# PMXAS5600N12_V1_0.net
KiCad netlist of a schematic drawn in EAGLE
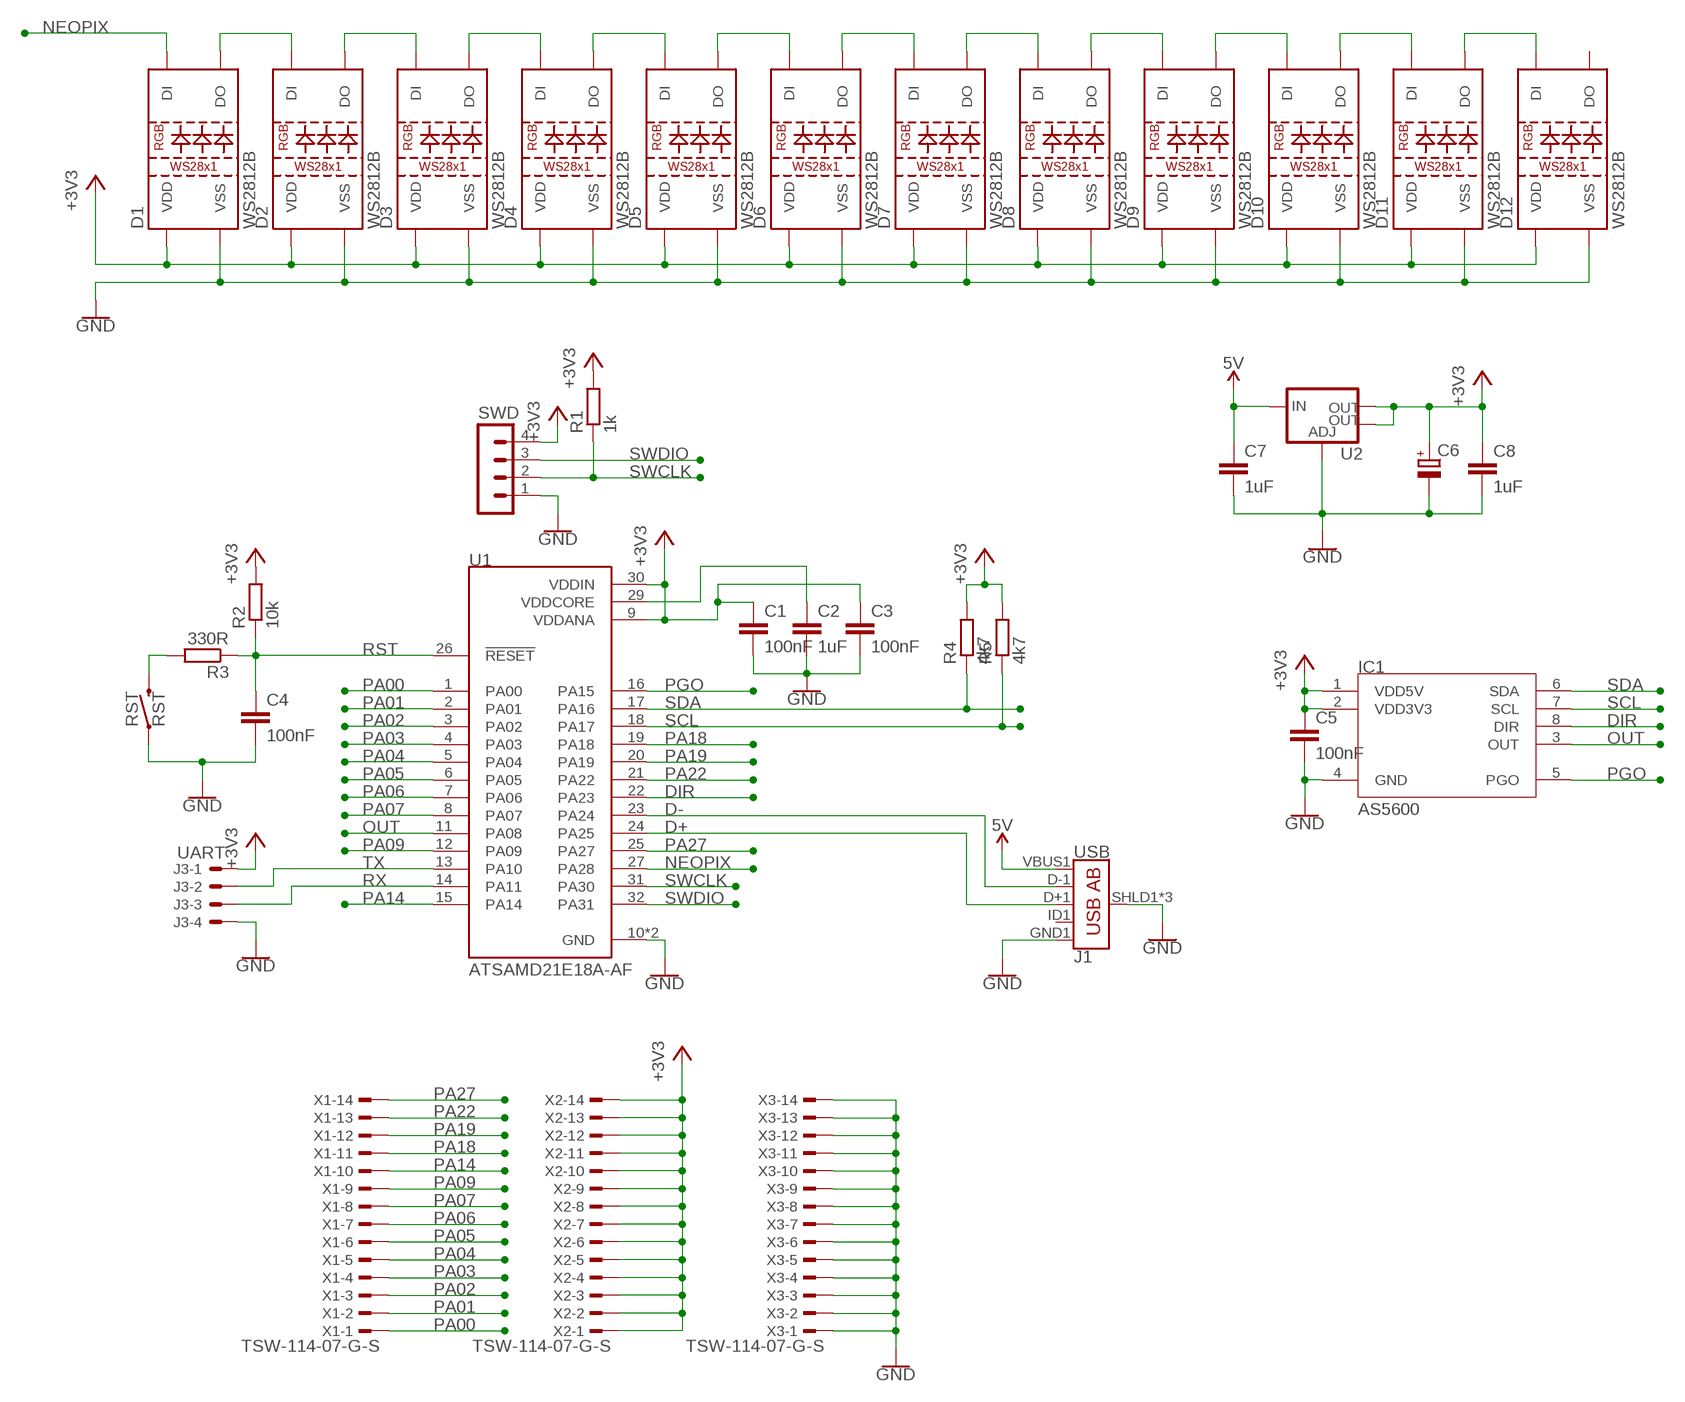
[diagram p0: schematic, sheet 1]

(export (version "E")
  (design (tool "Eeschema 10.0.6"))
  (components
    (comp (ref "C1")
      (value "100nF")
      (footprint "eagle-import:C0603")
      (libsource (lib "eagle-import") (part "C-EUC0603"))
    )
    (comp (ref "C2")
      (value "1uF")
      (footprint "eagle-import:C0603")
      (libsource (lib "eagle-import") (part "C-EUC0603"))
    )
    (comp (ref "C3")
      (value "100nF")
      (footprint "eagle-import:C0603")
      (libsource (lib "eagle-import") (part "C-EUC0603"))
    )
    (comp (ref "C4")
      (value "100nF")
      (footprint "eagle-import:C0603")
      (libsource (lib "eagle-import") (part "C-EUC0603"))
    )
    (comp (ref "C5")
      (value "100nF")
      (footprint "eagle-import:C0603")
      (libsource (lib "eagle-import") (part "C-EUC0603"))
    )
    (comp (ref "C6")
      (value "CPOL-EU153CLV-0605")
      (footprint "eagle-import:153CLV-0605")
      (libsource (lib "eagle-import") (part "CPOL-EU153CLV-0605"))
    )
    (comp (ref "C7")
      (value "1uF")
      (footprint "eagle-import:C0603")
      (libsource (lib "eagle-import") (part "C-EUC0603"))
    )
    (comp (ref "C8")
      (value "1uF")
      (footprint "eagle-import:C0603")
      (libsource (lib "eagle-import") (part "C-EUC0603"))
    )
    (comp (ref "D1")
      (value "WS2812B")
      (footprint "eagle-import:WS2812B")
      (libsource (lib "eagle-import") (part "WS2812B"))
    )
    (comp (ref "D2")
      (value "WS2812B")
      (footprint "eagle-import:WS2812B")
      (libsource (lib "eagle-import") (part "WS2812B"))
    )
    (comp (ref "D3")
      (value "WS2812B")
      (footprint "eagle-import:WS2812B")
      (libsource (lib "eagle-import") (part "WS2812B"))
    )
    (comp (ref "D4")
      (value "WS2812B")
      (footprint "eagle-import:WS2812B")
      (libsource (lib "eagle-import") (part "WS2812B"))
    )
    (comp (ref "D5")
      (value "WS2812B")
      (footprint "eagle-import:WS2812B")
      (libsource (lib "eagle-import") (part "WS2812B"))
    )
    (comp (ref "D6")
      (value "WS2812B")
      (footprint "eagle-import:WS2812B")
      (libsource (lib "eagle-import") (part "WS2812B"))
    )
    (comp (ref "D7")
      (value "WS2812B")
      (footprint "eagle-import:WS2812B")
      (libsource (lib "eagle-import") (part "WS2812B"))
    )
    (comp (ref "D8")
      (value "WS2812B")
      (footprint "eagle-import:WS2812B")
      (libsource (lib "eagle-import") (part "WS2812B"))
    )
    (comp (ref "D9")
      (value "WS2812B")
      (footprint "eagle-import:WS2812B")
      (libsource (lib "eagle-import") (part "WS2812B"))
    )
    (comp (ref "D10")
      (value "WS2812B")
      (footprint "eagle-import:WS2812B")
      (libsource (lib "eagle-import") (part "WS2812B"))
    )
    (comp (ref "D11")
      (value "WS2812B")
      (footprint "eagle-import:WS2812B")
      (libsource (lib "eagle-import") (part "WS2812B"))
    )
    (comp (ref "D12")
      (value "WS2812B")
      (footprint "eagle-import:WS2812B")
      (libsource (lib "eagle-import") (part "WS2812B"))
    )
    (comp (ref "IC1")
      (value "AS5600")
      (footprint "eagle-import:SOIC8")
      (libsource (lib "eagle-import") (part "AS5600"))
    )
    (comp (ref "J1")
      (value "USB")
      (footprint "eagle-import:USB-AB-MICRO-SMD")
      (libsource (lib "eagle-import") (part "USB_AB_SMT"))
    )
    (comp (ref "J3")
      (value "UART")
      (footprint "eagle-import:7395-04")
      (fields (field (name "MF") "MOLEX"))
      (libsource (lib "eagle-import") (part "22-?-0405-7048"))
    )
    (comp (ref "R1")
      (value "1k")
      (footprint "eagle-import:R0603")
      (libsource (lib "eagle-import") (part "R-EU_R0603"))
    )
    (comp (ref "R2")
      (value "10k")
      (footprint "eagle-import:R0603")
      (libsource (lib "eagle-import") (part "R-EU_R0603"))
    )
    (comp (ref "R3")
      (value "330R")
      (footprint "eagle-import:R0603")
      (libsource (lib "eagle-import") (part "R-EU_R0603"))
    )
    (comp (ref "R4")
      (value "4k7")
      (footprint "eagle-import:R0603")
      (libsource (lib "eagle-import") (part "R-EU_R0603"))
    )
    (comp (ref "R5")
      (value "4k7")
      (footprint "eagle-import:R0603")
      (libsource (lib "eagle-import") (part "R-EU_R0603"))
    )
    (comp (ref "RST")
      (value "RST")
      (footprint "eagle-import:TACTILE_SWITCH_SMD_5.2MM")
      (libsource (lib "eagle-import") (part "MOMENTARY-SWITCH-SPST-SMD-5.2MM"))
    )
    (comp (ref "SWD")
      (value "MA04-1")
      (footprint "eagle-import:MA04-1")
      (libsource (lib "eagle-import") (part "MA04-1"))
    )
    (comp (ref "U1")
      (value "ATSAMD21E18A-AF")
      (footprint "eagle-import:QFP80P900X900X120-32N")
      (fields (field (name "MF") "Microchip"))
      (libsource (lib "eagle-import") (part "ATSAMD21E18A-AF"))
    )
    (comp (ref "U2")
      (value "V_REG_LM1117SOT223")
      (footprint "eagle-import:SOT223")
      (libsource (lib "eagle-import") (part "V_REG_LM1117SOT223"))
    )
    (comp (ref "X1")
      (value "TSW-114-07-G-S")
      (footprint "eagle-import:TSW-114-XX-G-S")
      (fields (field (name "MF") "Samtec Inc."))
      (libsource (lib "eagle-import") (part "TSW-114--G-S07"))
    )
    (comp (ref "X2")
      (value "TSW-114-07-G-S")
      (footprint "eagle-import:TSW-114-XX-G-S")
      (fields (field (name "MF") "Samtec Inc."))
      (libsource (lib "eagle-import") (part "TSW-114--G-S07"))
    )
    (comp (ref "X3")
      (value "TSW-114-07-G-S")
      (footprint "eagle-import:TSW-114-XX-G-S")
      (fields (field (name "MF") "Samtec Inc."))
      (libsource (lib "eagle-import") (part "TSW-114--G-S07"))
    )
  )
  (nets
    (net (code "1") (name "+3V3") (class "Default")
      (node (ref "C1") (pin "1") (pinfunction "1_1") (pintype "passive"))
      (node (ref "C3") (pin "1") (pinfunction "1_1") (pintype "passive"))
      (node (ref "C5") (pin "1") (pinfunction "1_1") (pintype "passive"))
      (node (ref "C6") (pin "+") (pinfunction "+_+") (pintype "passive"))
      (node (ref "C8") (pin "1") (pinfunction "1_1") (pintype "passive"))
      (node (ref "D1") (pin "1") (pinfunction "VDD_1") (pintype "bidirectional"))
      (node (ref "D10") (pin "1") (pinfunction "VDD_1") (pintype "bidirectional"))
      (node (ref "D11") (pin "1") (pinfunction "VDD_1") (pintype "bidirectional"))
      (node (ref "D12") (pin "1") (pinfunction "VDD_1") (pintype "bidirectional"))
      (node (ref "D2") (pin "1") (pinfunction "VDD_1") (pintype "bidirectional"))
      (node (ref "D3") (pin "1") (pinfunction "VDD_1") (pintype "bidirectional"))
      (node (ref "D4") (pin "1") (pinfunction "VDD_1") (pintype "bidirectional"))
      (node (ref "D5") (pin "1") (pinfunction "VDD_1") (pintype "bidirectional"))
      (node (ref "D6") (pin "1") (pinfunction "VDD_1") (pintype "bidirectional"))
      (node (ref "D7") (pin "1") (pinfunction "VDD_1") (pintype "bidirectional"))
      (node (ref "D8") (pin "1") (pinfunction "VDD_1") (pintype "bidirectional"))
      (node (ref "D9") (pin "1") (pinfunction "VDD_1") (pintype "bidirectional"))
      (node (ref "IC1") (pin "1") (pinfunction "VDD5V_1") (pintype "bidirectional"))
      (node (ref "IC1") (pin "2") (pinfunction "VDD3V3_2") (pintype "bidirectional"))
      (node (ref "J3") (pin "1") (pinfunction "S_1") (pintype "passive"))
      (node (ref "R1") (pin "2") (pinfunction "2_2") (pintype "passive"))
      (node (ref "R2") (pin "2") (pinfunction "2_2") (pintype "passive"))
      (node (ref "R4") (pin "2") (pinfunction "2_2") (pintype "passive"))
      (node (ref "R5") (pin "2") (pinfunction "2_2") (pintype "passive"))
      (node (ref "SWD") (pin "4") (pinfunction "4_4") (pintype "passive"))
      (node (ref "U1") (pin "30") (pinfunction "VDDIN_30") (pintype "power_in"))
      (node (ref "U1") (pin "9") (pinfunction "VDDANA_9") (pintype "power_in"))
      (node (ref "U2") (pin "2") (pinfunction "OUT_2") (pintype "output"))
      (node (ref "U2") (pin "4") (pinfunction "OUT_4") (pintype "output"))
      (node (ref "X2") (pin "1") (pinfunction "1_1") (pintype "passive"))
      (node (ref "X2") (pin "10") (pinfunction "1_10") (pintype "passive"))
      (node (ref "X2") (pin "11") (pinfunction "1_11") (pintype "passive"))
      (node (ref "X2") (pin "12") (pinfunction "1_12") (pintype "passive"))
      (node (ref "X2") (pin "13") (pinfunction "1_13") (pintype "passive"))
      (node (ref "X2") (pin "14") (pinfunction "1_14") (pintype "passive"))
      (node (ref "X2") (pin "2") (pinfunction "1_2") (pintype "passive"))
      (node (ref "X2") (pin "3") (pinfunction "1_3") (pintype "passive"))
      (node (ref "X2") (pin "4") (pinfunction "1_4") (pintype "passive"))
      (node (ref "X2") (pin "5") (pinfunction "1_5") (pintype "passive"))
      (node (ref "X2") (pin "6") (pinfunction "1_6") (pintype "passive"))
      (node (ref "X2") (pin "7") (pinfunction "1_7") (pintype "passive"))
      (node (ref "X2") (pin "8") (pinfunction "1_8") (pintype "passive"))
      (node (ref "X2") (pin "9") (pinfunction "1_9") (pintype "passive"))
    )
    (net (code "2") (name "/D+") (class "Default")
      (node (ref "J1") (pin "D+1") (pinfunction "D+_D+1") (pintype "bidirectional"))
      (node (ref "U1") (pin "24") (pinfunction "PA25_24") (pintype "bidirectional"))
    )
    (net (code "3") (name "/D-") (class "Default")
      (node (ref "J1") (pin "D-1") (pinfunction "D-_D-1") (pintype "bidirectional"))
      (node (ref "U1") (pin "23") (pinfunction "PA24_23") (pintype "bidirectional"))
    )
    (net (code "4") (name "/DIR") (class "Default")
      (node (ref "IC1") (pin "8") (pinfunction "DIR_8") (pintype "bidirectional"))
      (node (ref "U1") (pin "22") (pinfunction "PA23_22") (pintype "bidirectional"))
    )
    (net (code "5") (name "/NEOPIX") (class "Default")
      (node (ref "D1") (pin "4") (pinfunction "DI_4") (pintype "bidirectional"))
      (node (ref "U1") (pin "27") (pinfunction "PA28_27") (pintype "bidirectional"))
    )
    (net (code "6") (name "/OUT") (class "Default")
      (node (ref "IC1") (pin "3") (pinfunction "OUT_3") (pintype "bidirectional"))
      (node (ref "U1") (pin "11") (pinfunction "PA08_11") (pintype "bidirectional"))
    )
    (net (code "7") (name "/PA00") (class "Default")
      (node (ref "U1") (pin "1") (pinfunction "PA00_1") (pintype "bidirectional"))
      (node (ref "X1") (pin "1") (pinfunction "1_1") (pintype "passive"))
    )
    (net (code "8") (name "/PA01") (class "Default")
      (node (ref "U1") (pin "2") (pinfunction "PA01_2") (pintype "bidirectional"))
      (node (ref "X1") (pin "2") (pinfunction "1_2") (pintype "passive"))
    )
    (net (code "9") (name "/PA02") (class "Default")
      (node (ref "U1") (pin "3") (pinfunction "PA02_3") (pintype "bidirectional"))
      (node (ref "X1") (pin "3") (pinfunction "1_3") (pintype "passive"))
    )
    (net (code "10") (name "/PA03") (class "Default")
      (node (ref "U1") (pin "4") (pinfunction "PA03_4") (pintype "bidirectional"))
      (node (ref "X1") (pin "4") (pinfunction "1_4") (pintype "passive"))
    )
    (net (code "11") (name "/PA04") (class "Default")
      (node (ref "U1") (pin "5") (pinfunction "PA04_5") (pintype "bidirectional"))
      (node (ref "X1") (pin "5") (pinfunction "1_5") (pintype "passive"))
    )
    (net (code "12") (name "/PA05") (class "Default")
      (node (ref "U1") (pin "6") (pinfunction "PA05_6") (pintype "bidirectional"))
      (node (ref "X1") (pin "6") (pinfunction "1_6") (pintype "passive"))
    )
    (net (code "13") (name "/PA06") (class "Default")
      (node (ref "U1") (pin "7") (pinfunction "PA06_7") (pintype "bidirectional"))
      (node (ref "X1") (pin "7") (pinfunction "1_7") (pintype "passive"))
    )
    (net (code "14") (name "/PA07") (class "Default")
      (node (ref "U1") (pin "8") (pinfunction "PA07_8") (pintype "bidirectional"))
      (node (ref "X1") (pin "8") (pinfunction "1_8") (pintype "passive"))
    )
    (net (code "15") (name "/PA09") (class "Default")
      (node (ref "U1") (pin "12") (pinfunction "PA09_12") (pintype "bidirectional"))
      (node (ref "X1") (pin "9") (pinfunction "1_9") (pintype "passive"))
    )
    (net (code "16") (name "/PA14") (class "Default")
      (node (ref "U1") (pin "15") (pinfunction "PA14_15") (pintype "bidirectional"))
      (node (ref "X1") (pin "10") (pinfunction "1_10") (pintype "passive"))
    )
    (net (code "17") (name "/PA18") (class "Default")
      (node (ref "U1") (pin "19") (pinfunction "PA18_19") (pintype "bidirectional"))
      (node (ref "X1") (pin "11") (pinfunction "1_11") (pintype "passive"))
    )
    (net (code "18") (name "/PA19") (class "Default")
      (node (ref "U1") (pin "20") (pinfunction "PA19_20") (pintype "bidirectional"))
      (node (ref "X1") (pin "12") (pinfunction "1_12") (pintype "passive"))
    )
    (net (code "19") (name "/PA22") (class "Default")
      (node (ref "U1") (pin "21") (pinfunction "PA22_21") (pintype "bidirectional"))
      (node (ref "X1") (pin "13") (pinfunction "1_13") (pintype "passive"))
    )
    (net (code "20") (name "/PA27") (class "Default")
      (node (ref "U1") (pin "25") (pinfunction "PA27_25") (pintype "bidirectional"))
      (node (ref "X1") (pin "14") (pinfunction "1_14") (pintype "passive"))
    )
    (net (code "21") (name "/PGO") (class "Default")
      (node (ref "IC1") (pin "5") (pinfunction "PGO_5") (pintype "bidirectional"))
      (node (ref "U1") (pin "16") (pinfunction "PA15_16") (pintype "bidirectional"))
    )
    (net (code "22") (name "/RST") (class "Default")
      (node (ref "C4") (pin "1") (pinfunction "1_1") (pintype "passive"))
      (node (ref "R2") (pin "1") (pinfunction "1_1") (pintype "passive"))
      (node (ref "R3") (pin "1") (pinfunction "1_1") (pintype "passive"))
      (node (ref "U1") (pin "26") (pinfunction "~{RESET}_26") (pintype "input"))
    )
    (net (code "23") (name "/RX") (class "Default")
      (node (ref "J3") (pin "3") (pinfunction "S_3") (pintype "passive"))
      (node (ref "U1") (pin "14") (pinfunction "PA11_14") (pintype "bidirectional"))
    )
    (net (code "24") (name "/SCL") (class "Default")
      (node (ref "IC1") (pin "7") (pinfunction "SCL_7") (pintype "bidirectional"))
      (node (ref "R5") (pin "1") (pinfunction "1_1") (pintype "passive"))
      (node (ref "U1") (pin "18") (pinfunction "PA17_18") (pintype "bidirectional"))
    )
    (net (code "25") (name "/SDA") (class "Default")
      (node (ref "IC1") (pin "6") (pinfunction "SDA_6") (pintype "bidirectional"))
      (node (ref "R4") (pin "1") (pinfunction "1_1") (pintype "passive"))
      (node (ref "U1") (pin "17") (pinfunction "PA16_17") (pintype "bidirectional"))
    )
    (net (code "26") (name "/SWCLK") (class "Default")
      (node (ref "R1") (pin "1") (pinfunction "1_1") (pintype "passive"))
      (node (ref "SWD") (pin "2") (pinfunction "2_2") (pintype "passive"))
      (node (ref "U1") (pin "31") (pinfunction "PA30_31") (pintype "bidirectional"))
    )
    (net (code "27") (name "/SWDIO") (class "Default")
      (node (ref "SWD") (pin "3") (pinfunction "3_3") (pintype "passive"))
      (node (ref "U1") (pin "32") (pinfunction "PA31_32") (pintype "bidirectional"))
    )
    (net (code "28") (name "/TX") (class "Default")
      (node (ref "J3") (pin "2") (pinfunction "S_2") (pintype "passive"))
      (node (ref "U1") (pin "13") (pinfunction "PA10_13") (pintype "bidirectional"))
    )
    (net (code "29") (name "5V") (class "Default")
      (node (ref "C7") (pin "1") (pinfunction "1_1") (pintype "passive"))
      (node (ref "J1") (pin "VBUS1") (pinfunction "VBUS_VBUS1") (pintype "power_in"))
      (node (ref "U2") (pin "3") (pinfunction "IN_3") (pintype "input"))
    )
    (net (code "30") (name "GND") (class "Default")
      (node (ref "C1") (pin "2") (pinfunction "2_2") (pintype "passive"))
      (node (ref "C2") (pin "2") (pinfunction "2_2") (pintype "passive"))
      (node (ref "C3") (pin "2") (pinfunction "2_2") (pintype "passive"))
      (node (ref "C4") (pin "2") (pinfunction "2_2") (pintype "passive"))
      (node (ref "C5") (pin "2") (pinfunction "2_2") (pintype "passive"))
      (node (ref "C6") (pin "-") (pinfunction "-_-") (pintype "passive"))
      (node (ref "C7") (pin "2") (pinfunction "2_2") (pintype "passive"))
      (node (ref "C8") (pin "2") (pinfunction "2_2") (pintype "passive"))
      (node (ref "D1") (pin "3") (pinfunction "VSS_3") (pintype "bidirectional"))
      (node (ref "D10") (pin "3") (pinfunction "VSS_3") (pintype "bidirectional"))
      (node (ref "D11") (pin "3") (pinfunction "VSS_3") (pintype "bidirectional"))
      (node (ref "D12") (pin "3") (pinfunction "VSS_3") (pintype "bidirectional"))
      (node (ref "D2") (pin "3") (pinfunction "VSS_3") (pintype "bidirectional"))
      (node (ref "D3") (pin "3") (pinfunction "VSS_3") (pintype "bidirectional"))
      (node (ref "D4") (pin "3") (pinfunction "VSS_3") (pintype "bidirectional"))
      (node (ref "D5") (pin "3") (pinfunction "VSS_3") (pintype "bidirectional"))
      (node (ref "D6") (pin "3") (pinfunction "VSS_3") (pintype "bidirectional"))
      (node (ref "D7") (pin "3") (pinfunction "VSS_3") (pintype "bidirectional"))
      (node (ref "D8") (pin "3") (pinfunction "VSS_3") (pintype "bidirectional"))
      (node (ref "D9") (pin "3") (pinfunction "VSS_3") (pintype "bidirectional"))
      (node (ref "IC1") (pin "4") (pinfunction "GND_4") (pintype "bidirectional"))
      (node (ref "J1") (pin "GND1") (pinfunction "GND_GND1") (pintype "power_in"))
      (node (ref "J1") (pin "SHLD1") (pinfunction "SHIELD_SHLD1") (pintype "bidirectional"))
      (node (ref "J1") (pin "SHLD2") (pinfunction "SHIELD_SHLD2") (pintype "bidirectional"))
      (node (ref "J1") (pin "SHLD3") (pinfunction "SHIELD_SHLD3") (pintype "bidirectional"))
      (node (ref "J3") (pin "4") (pinfunction "S_4") (pintype "passive"))
      (node (ref "RST") (pin "1") (pinfunction "1_1") (pintype "passive"))
      (node (ref "SWD") (pin "1") (pinfunction "1_1") (pintype "passive"))
      (node (ref "U1") (pin "10") (pinfunction "GND_10") (pintype "power_in"))
      (node (ref "U1") (pin "28") (pinfunction "GND_28") (pintype "power_in"))
      (node (ref "U2") (pin "1") (pinfunction "ADJ_1") (pintype "input"))
      (node (ref "X3") (pin "1") (pinfunction "1_1") (pintype "passive"))
      (node (ref "X3") (pin "10") (pinfunction "1_10") (pintype "passive"))
      (node (ref "X3") (pin "11") (pinfunction "1_11") (pintype "passive"))
      (node (ref "X3") (pin "12") (pinfunction "1_12") (pintype "passive"))
      (node (ref "X3") (pin "13") (pinfunction "1_13") (pintype "passive"))
      (node (ref "X3") (pin "14") (pinfunction "1_14") (pintype "passive"))
      (node (ref "X3") (pin "2") (pinfunction "1_2") (pintype "passive"))
      (node (ref "X3") (pin "3") (pinfunction "1_3") (pintype "passive"))
      (node (ref "X3") (pin "4") (pinfunction "1_4") (pintype "passive"))
      (node (ref "X3") (pin "5") (pinfunction "1_5") (pintype "passive"))
      (node (ref "X3") (pin "6") (pinfunction "1_6") (pintype "passive"))
      (node (ref "X3") (pin "7") (pinfunction "1_7") (pintype "passive"))
      (node (ref "X3") (pin "8") (pinfunction "1_8") (pintype "passive"))
      (node (ref "X3") (pin "9") (pinfunction "1_9") (pintype "passive"))
    )
    (net (code "31") (name "Net-(D1-DO)") (class "Default")
      (node (ref "D1") (pin "2") (pinfunction "DO_2") (pintype "bidirectional"))
      (node (ref "D2") (pin "4") (pinfunction "DI_4") (pintype "bidirectional"))
    )
    (net (code "32") (name "Net-(D2-DO)") (class "Default")
      (node (ref "D2") (pin "2") (pinfunction "DO_2") (pintype "bidirectional"))
      (node (ref "D3") (pin "4") (pinfunction "DI_4") (pintype "bidirectional"))
    )
    (net (code "33") (name "Net-(D3-DO)") (class "Default")
      (node (ref "D3") (pin "2") (pinfunction "DO_2") (pintype "bidirectional"))
      (node (ref "D4") (pin "4") (pinfunction "DI_4") (pintype "bidirectional"))
    )
    (net (code "34") (name "Net-(D4-DO)") (class "Default")
      (node (ref "D4") (pin "2") (pinfunction "DO_2") (pintype "bidirectional"))
      (node (ref "D5") (pin "4") (pinfunction "DI_4") (pintype "bidirectional"))
    )
    (net (code "35") (name "Net-(D5-DO)") (class "Default")
      (node (ref "D5") (pin "2") (pinfunction "DO_2") (pintype "bidirectional"))
      (node (ref "D6") (pin "4") (pinfunction "DI_4") (pintype "bidirectional"))
    )
    (net (code "36") (name "Net-(D6-DO)") (class "Default")
      (node (ref "D6") (pin "2") (pinfunction "DO_2") (pintype "bidirectional"))
      (node (ref "D7") (pin "4") (pinfunction "DI_4") (pintype "bidirectional"))
    )
    (net (code "37") (name "Net-(D7-DO)") (class "Default")
      (node (ref "D7") (pin "2") (pinfunction "DO_2") (pintype "bidirectional"))
      (node (ref "D8") (pin "4") (pinfunction "DI_4") (pintype "bidirectional"))
    )
    (net (code "38") (name "Net-(D8-DO)") (class "Default")
      (node (ref "D8") (pin "2") (pinfunction "DO_2") (pintype "bidirectional"))
      (node (ref "D9") (pin "4") (pinfunction "DI_4") (pintype "bidirectional"))
    )
    (net (code "39") (name "Net-(D10-DI)") (class "Default")
      (node (ref "D10") (pin "4") (pinfunction "DI_4") (pintype "bidirectional"))
      (node (ref "D9") (pin "2") (pinfunction "DO_2") (pintype "bidirectional"))
    )
    (net (code "40") (name "Net-(D10-DO)") (class "Default")
      (node (ref "D10") (pin "2") (pinfunction "DO_2") (pintype "bidirectional"))
      (node (ref "D11") (pin "4") (pinfunction "DI_4") (pintype "bidirectional"))
    )
    (net (code "41") (name "Net-(D11-DO)") (class "Default")
      (node (ref "D11") (pin "2") (pinfunction "DO_2") (pintype "bidirectional"))
      (node (ref "D12") (pin "4") (pinfunction "DI_4") (pintype "bidirectional"))
    )
    (net (code "42") (name "Net-(RST-2)") (class "Default")
      (node (ref "R3") (pin "2") (pinfunction "2_2") (pintype "passive"))
      (node (ref "RST") (pin "3") (pinfunction "2_3") (pintype "passive"))
    )
    (net (code "43") (name "Net-(U1-VDDCORE)") (class "Default")
      (node (ref "C2") (pin "1") (pinfunction "1_1") (pintype "passive"))
      (node (ref "U1") (pin "29") (pinfunction "VDDCORE_29") (pintype "power_in"))
    )
    (net (code "44") (name "unconnected-(D12-DO-Pad2)") (class "Default")
      (node (ref "D12") (pin "2") (pinfunction "DO_2") (pintype "bidirectional"))
    )
    (net (code "45") (name "unconnected-(J1-USBID-PadID1)") (class "Default")
      (node (ref "J1") (pin "ID1") (pinfunction "USBID_ID1") (pintype "bidirectional"))
    )
  )
)
